# servo_tester.net
KiCad netlist of a schematic drawn in EAGLE
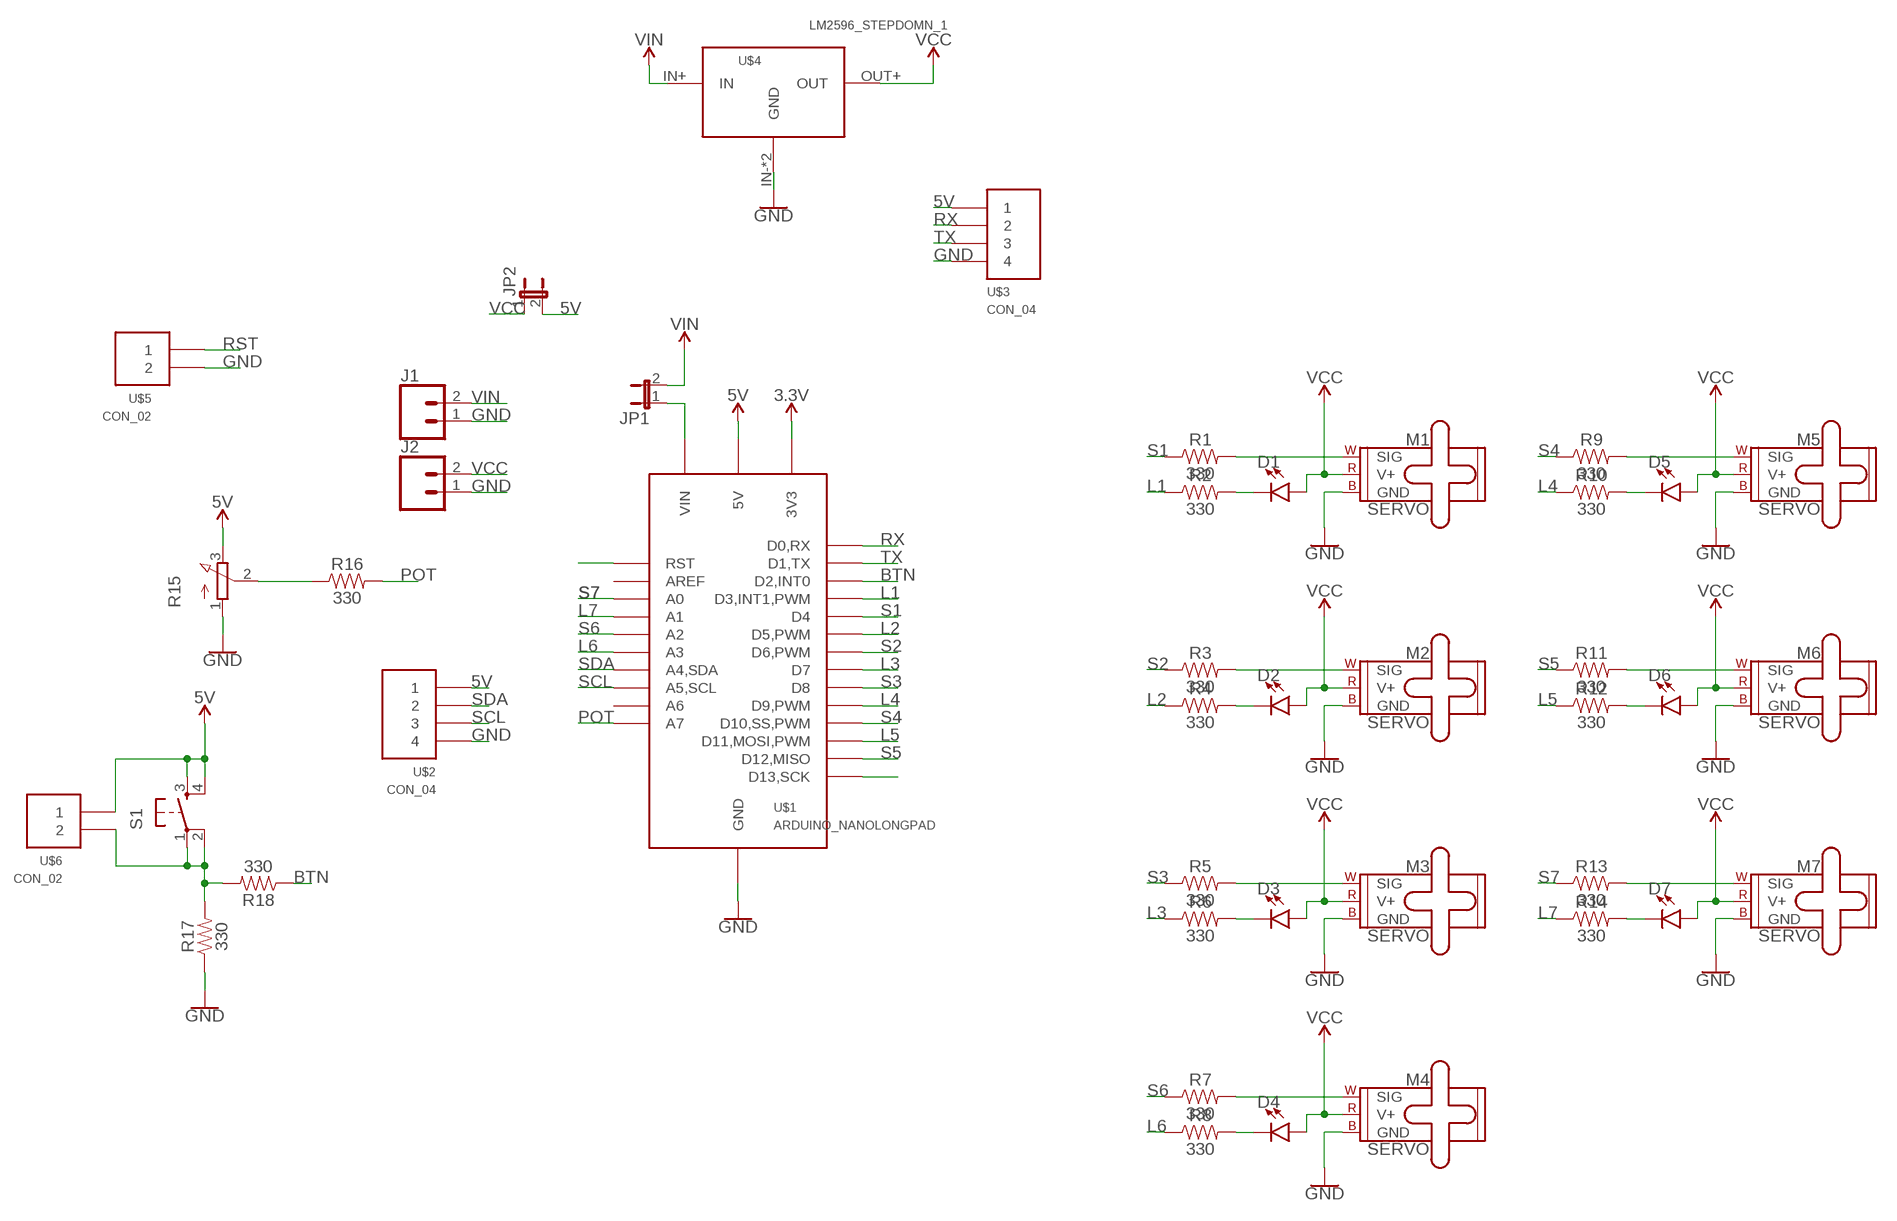
[diagram p0: schematic, sheet 1]

(export (version "E")
  (design (tool "Eeschema 10.0.6"))
  (components
    (comp (ref "D1")
      (value "LED3MM")
      (footprint "eagle-import:LED_3MM")
      (libsource (lib "eagle-import") (part "LED3MM"))
    )
    (comp (ref "D2")
      (value "LED3MM")
      (footprint "eagle-import:LED_3MM")
      (libsource (lib "eagle-import") (part "LED3MM"))
    )
    (comp (ref "D3")
      (value "LED3MM")
      (footprint "eagle-import:LED_3MM")
      (libsource (lib "eagle-import") (part "LED3MM"))
    )
    (comp (ref "D4")
      (value "LED3MM")
      (footprint "eagle-import:LED_3MM")
      (libsource (lib "eagle-import") (part "LED3MM"))
    )
    (comp (ref "D5")
      (value "LED3MM")
      (footprint "eagle-import:LED_3MM")
      (libsource (lib "eagle-import") (part "LED3MM"))
    )
    (comp (ref "D6")
      (value "LED3MM")
      (footprint "eagle-import:LED_3MM")
      (libsource (lib "eagle-import") (part "LED3MM"))
    )
    (comp (ref "D7")
      (value "LED3MM")
      (footprint "eagle-import:LED_3MM")
      (libsource (lib "eagle-import") (part "LED3MM"))
    )
    (comp (ref "J1")
      (value "CONN_025MM")
      (footprint "eagle-import:SCREWTERMINAL-5MM-2")
      (libsource (lib "eagle-import") (part "CONN_025MM"))
    )
    (comp (ref "J2")
      (value "CONN_025MM")
      (footprint "eagle-import:SCREWTERMINAL-5MM-2")
      (libsource (lib "eagle-import") (part "CONN_025MM"))
    )
    (comp (ref "JP1")
      (value "JUMPER-2PTH")
      (footprint "eagle-import:1X02")
      (libsource (lib "eagle-import") (part "JUMPER-2PTH"))
    )
    (comp (ref "JP2")
      (value "JUMPER-2PTH")
      (footprint "eagle-import:1X02")
      (libsource (lib "eagle-import") (part "JUMPER-2PTH"))
    )
    (comp (ref "M1")
      (value "SERVO")
      (footprint "eagle-import:1X03")
      (libsource (lib "eagle-import") (part "SERVO"))
    )
    (comp (ref "M2")
      (value "SERVO")
      (footprint "eagle-import:1X03")
      (libsource (lib "eagle-import") (part "SERVO"))
    )
    (comp (ref "M3")
      (value "SERVO")
      (footprint "eagle-import:1X03")
      (libsource (lib "eagle-import") (part "SERVO"))
    )
    (comp (ref "M4")
      (value "SERVO")
      (footprint "eagle-import:1X03")
      (libsource (lib "eagle-import") (part "SERVO"))
    )
    (comp (ref "M5")
      (value "SERVO")
      (footprint "eagle-import:1X03")
      (libsource (lib "eagle-import") (part "SERVO"))
    )
    (comp (ref "M6")
      (value "SERVO")
      (footprint "eagle-import:1X03")
      (libsource (lib "eagle-import") (part "SERVO"))
    )
    (comp (ref "M7")
      (value "SERVO")
      (footprint "eagle-import:1X03")
      (libsource (lib "eagle-import") (part "SERVO"))
    )
    (comp (ref "R1")
      (value "330")
      (footprint "eagle-import:0603")
      (libsource (lib "eagle-import") (part "330OHM-0603-1/10W-1%"))
    )
    (comp (ref "R2")
      (value "330")
      (footprint "eagle-import:0603")
      (libsource (lib "eagle-import") (part "330OHM-0603-1/10W-1%"))
    )
    (comp (ref "R3")
      (value "330")
      (footprint "eagle-import:0603")
      (libsource (lib "eagle-import") (part "330OHM-0603-1/10W-1%"))
    )
    (comp (ref "R4")
      (value "330")
      (footprint "eagle-import:0603")
      (libsource (lib "eagle-import") (part "330OHM-0603-1/10W-1%"))
    )
    (comp (ref "R5")
      (value "330")
      (footprint "eagle-import:0603")
      (libsource (lib "eagle-import") (part "330OHM-0603-1/10W-1%"))
    )
    (comp (ref "R6")
      (value "330")
      (footprint "eagle-import:0603")
      (libsource (lib "eagle-import") (part "330OHM-0603-1/10W-1%"))
    )
    (comp (ref "R7")
      (value "330")
      (footprint "eagle-import:0603")
      (libsource (lib "eagle-import") (part "330OHM-0603-1/10W-1%"))
    )
    (comp (ref "R8")
      (value "330")
      (footprint "eagle-import:0603")
      (libsource (lib "eagle-import") (part "330OHM-0603-1/10W-1%"))
    )
    (comp (ref "R9")
      (value "330")
      (footprint "eagle-import:0603")
      (libsource (lib "eagle-import") (part "330OHM-0603-1/10W-1%"))
    )
    (comp (ref "R10")
      (value "330")
      (footprint "eagle-import:0603")
      (libsource (lib "eagle-import") (part "330OHM-0603-1/10W-1%"))
    )
    (comp (ref "R11")
      (value "330")
      (footprint "eagle-import:0603")
      (libsource (lib "eagle-import") (part "330OHM-0603-1/10W-1%"))
    )
    (comp (ref "R12")
      (value "330")
      (footprint "eagle-import:0603")
      (libsource (lib "eagle-import") (part "330OHM-0603-1/10W-1%"))
    )
    (comp (ref "R13")
      (value "330")
      (footprint "eagle-import:0603")
      (libsource (lib "eagle-import") (part "330OHM-0603-1/10W-1%"))
    )
    (comp (ref "R14")
      (value "330")
      (footprint "eagle-import:0603")
      (libsource (lib "eagle-import") (part "330OHM-0603-1/10W-1%"))
    )
    (comp (ref "R15")
      (value "3RP/1610N")
      (footprint "eagle-import:3RP_1610N")
      (libsource (lib "eagle-import") (part "3RP/1610N"))
    )
    (comp (ref "R16")
      (value "330")
      (footprint "eagle-import:0603")
      (libsource (lib "eagle-import") (part "330OHM-0603-1/10W-1%"))
    )
    (comp (ref "R17")
      (value "330")
      (footprint "eagle-import:0603")
      (libsource (lib "eagle-import") (part "330OHM-0603-1/10W-1%"))
    )
    (comp (ref "R18")
      (value "330")
      (footprint "eagle-import:0603")
      (libsource (lib "eagle-import") (part "330OHM-0603-1/10W-1%"))
    )
    (comp (ref "S1")
      (value "TAC_SWITCHPTH")
      (footprint "eagle-import:TACTILE-PTH")
      (libsource (lib "eagle-import") (part "TAC_SWITCHPTH"))
    )
    (comp (ref "U$1")
      (value "ARDUINO_NANOLONGPAD")
      (footprint "eagle-import:ARDUINO_MANO_LONGPAD")
      (libsource (lib "eagle-import") (part "ARDUINO_NANOLONGPAD"))
    )
    (comp (ref "U$2")
      (value "CON_04")
      (footprint "eagle-import:4-PIN")
      (libsource (lib "eagle-import") (part "CON_04"))
    )
    (comp (ref "U$3")
      (value "CON_04")
      (footprint "eagle-import:4-PIN")
      (libsource (lib "eagle-import") (part "CON_04"))
    )
    (comp (ref "U$4")
      (value "LM2596_STEPDOMN_1")
      (footprint "eagle-import:STEPDOWN_1")
      (libsource (lib "eagle-import") (part "LM2596_STEPDOMN_1"))
    )
    (comp (ref "U$5")
      (value "CON_02")
      (footprint "eagle-import:2-PIN")
      (libsource (lib "eagle-import") (part "CON_02"))
    )
    (comp (ref "U$6")
      (value "CON_02")
      (footprint "eagle-import:2-PIN")
      (libsource (lib "eagle-import") (part "CON_02"))
    )
  )
  (nets
    (net (code "1") (name "/BTN") (class "Default")
      (node (ref "R18") (pin "1") (pinfunction "1_1") (pintype "passive"))
      (node (ref "U$1") (pin "D2") (pinfunction "D2,INT0_D2") (pintype "bidirectional"))
    )
    (net (code "2") (name "/L1") (class "Default")
      (node (ref "R2") (pin "1") (pinfunction "1_1") (pintype "passive"))
      (node (ref "U$1") (pin "D3") (pinfunction "D3,INT1,PWM_D3") (pintype "bidirectional"))
    )
    (net (code "3") (name "/L2") (class "Default")
      (node (ref "R4") (pin "1") (pinfunction "1_1") (pintype "passive"))
      (node (ref "U$1") (pin "D5") (pinfunction "D5,PWM_D5") (pintype "bidirectional"))
    )
    (net (code "4") (name "/L3") (class "Default")
      (node (ref "R6") (pin "1") (pinfunction "1_1") (pintype "passive"))
      (node (ref "U$1") (pin "D7") (pinfunction "D7_D7") (pintype "bidirectional"))
    )
    (net (code "5") (name "/L4") (class "Default")
      (node (ref "R10") (pin "1") (pinfunction "1_1") (pintype "passive"))
      (node (ref "U$1") (pin "D9") (pinfunction "D9,PWM_D9") (pintype "bidirectional"))
    )
    (net (code "6") (name "/L5") (class "Default")
      (node (ref "R12") (pin "1") (pinfunction "1_1") (pintype "passive"))
      (node (ref "U$1") (pin "D11") (pinfunction "D11,MOSI,PWM_D11") (pintype "bidirectional"))
    )
    (net (code "7") (name "/L6") (class "Default")
      (node (ref "R8") (pin "1") (pinfunction "1_1") (pintype "passive"))
      (node (ref "U$1") (pin "A3") (pinfunction "A3_A3") (pintype "bidirectional"))
    )
    (net (code "8") (name "/L7") (class "Default")
      (node (ref "R14") (pin "1") (pinfunction "1_1") (pintype "passive"))
      (node (ref "U$1") (pin "A1") (pinfunction "A1_A1") (pintype "bidirectional"))
    )
    (net (code "9") (name "/POT") (class "Default")
      (node (ref "R16") (pin "2") (pinfunction "2_2") (pintype "passive"))
      (node (ref "U$1") (pin "A7") (pinfunction "A7_A7") (pintype "bidirectional"))
    )
    (net (code "10") (name "/RST") (class "Default")
      (node (ref "U$1") (pin "RST@1") (pinfunction "RST_RST@1") (pintype "bidirectional"))
      (node (ref "U$1") (pin "RST@2") (pinfunction "RST_RST@2") (pintype "bidirectional"))
      (node (ref "U$5") (pin "1") (pinfunction "1_1") (pintype "bidirectional"))
    )
    (net (code "11") (name "/RX") (class "Default")
      (node (ref "U$1") (pin "RX0") (pinfunction "D0,RX_RX0") (pintype "bidirectional"))
      (node (ref "U$3") (pin "2") (pinfunction "2_2") (pintype "bidirectional"))
    )
    (net (code "12") (name "/S1") (class "Default")
      (node (ref "R1") (pin "1") (pinfunction "1_1") (pintype "passive"))
      (node (ref "U$1") (pin "D4") (pinfunction "D4_D4") (pintype "bidirectional"))
    )
    (net (code "13") (name "/S2") (class "Default")
      (node (ref "R3") (pin "1") (pinfunction "1_1") (pintype "passive"))
      (node (ref "U$1") (pin "D6") (pinfunction "D6,PWM_D6") (pintype "bidirectional"))
    )
    (net (code "14") (name "/S3") (class "Default")
      (node (ref "R5") (pin "1") (pinfunction "1_1") (pintype "passive"))
      (node (ref "U$1") (pin "D8") (pinfunction "D8_D8") (pintype "bidirectional"))
    )
    (net (code "15") (name "/S4") (class "Default")
      (node (ref "R9") (pin "1") (pinfunction "1_1") (pintype "passive"))
      (node (ref "U$1") (pin "D10") (pinfunction "D10,SS,PWM_D10") (pintype "bidirectional"))
    )
    (net (code "16") (name "/S5") (class "Default")
      (node (ref "R11") (pin "1") (pinfunction "1_1") (pintype "passive"))
      (node (ref "U$1") (pin "D12") (pinfunction "D12,MISO_D12") (pintype "bidirectional"))
    )
    (net (code "17") (name "/S6") (class "Default")
      (node (ref "R7") (pin "1") (pinfunction "1_1") (pintype "passive"))
      (node (ref "U$1") (pin "A2") (pinfunction "A2_A2") (pintype "bidirectional"))
    )
    (net (code "18") (name "/S7") (class "Default")
      (node (ref "R13") (pin "1") (pinfunction "1_1") (pintype "passive"))
      (node (ref "U$1") (pin "A0") (pinfunction "A0_A0") (pintype "bidirectional"))
    )
    (net (code "19") (name "/SCL") (class "Default")
      (node (ref "U$1") (pin "A5") (pinfunction "A5,SCL_A5") (pintype "bidirectional"))
      (node (ref "U$2") (pin "3") (pinfunction "3_3") (pintype "bidirectional"))
    )
    (net (code "20") (name "/SDA") (class "Default")
      (node (ref "U$1") (pin "A4") (pinfunction "A4,SDA_A4") (pintype "bidirectional"))
      (node (ref "U$2") (pin "2") (pinfunction "2_2") (pintype "bidirectional"))
    )
    (net (code "21") (name "/TX") (class "Default")
      (node (ref "U$1") (pin "TX1") (pinfunction "D1,TX_TX1") (pintype "bidirectional"))
      (node (ref "U$3") (pin "3") (pinfunction "3_3") (pintype "bidirectional"))
    )
    (net (code "22") (name "3.3V") (class "Default")
      (node (ref "U$1") (pin "3V3") (pinfunction "3V3_3V3") (pintype "bidirectional"))
    )
    (net (code "23") (name "5V") (class "Default")
      (node (ref "JP2") (pin "2") (pinfunction "2_2") (pintype "passive"))
      (node (ref "R15") (pin "3") (pinfunction "E_3") (pintype "passive"))
      (node (ref "S1") (pin "3") (pinfunction "3_3") (pintype "passive"))
      (node (ref "S1") (pin "4") (pinfunction "4_4") (pintype "passive"))
      (node (ref "U$1") (pin "5V") (pinfunction "5V_5V") (pintype "bidirectional"))
      (node (ref "U$2") (pin "1") (pinfunction "1_1") (pintype "bidirectional"))
      (node (ref "U$3") (pin "1") (pinfunction "1_1") (pintype "bidirectional"))
      (node (ref "U$6") (pin "1") (pinfunction "1_1") (pintype "bidirectional"))
    )
    (net (code "24") (name "GND") (class "Default")
      (node (ref "J1") (pin "1") (pinfunction "1_1") (pintype "passive"))
      (node (ref "J2") (pin "1") (pinfunction "1_1") (pintype "passive"))
      (node (ref "M1") (pin "3") (pinfunction "GND_3") (pintype "bidirectional"))
      (node (ref "M2") (pin "3") (pinfunction "GND_3") (pintype "bidirectional"))
      (node (ref "M3") (pin "3") (pinfunction "GND_3") (pintype "bidirectional"))
      (node (ref "M4") (pin "3") (pinfunction "GND_3") (pintype "bidirectional"))
      (node (ref "M5") (pin "3") (pinfunction "GND_3") (pintype "bidirectional"))
      (node (ref "M6") (pin "3") (pinfunction "GND_3") (pintype "bidirectional"))
      (node (ref "M7") (pin "3") (pinfunction "GND_3") (pintype "bidirectional"))
      (node (ref "R15") (pin "1") (pinfunction "A_1") (pintype "passive"))
      (node (ref "R17") (pin "1") (pinfunction "1_1") (pintype "passive"))
      (node (ref "U$1") (pin "GND@1") (pinfunction "GND_GND@1") (pintype "bidirectional"))
      (node (ref "U$1") (pin "GND@2") (pinfunction "GND_GND@2") (pintype "bidirectional"))
      (node (ref "U$2") (pin "4") (pinfunction "4_4") (pintype "bidirectional"))
      (node (ref "U$3") (pin "4") (pinfunction "4_4") (pintype "bidirectional"))
      (node (ref "U$4") (pin "IN-") (pinfunction "GND_IN-") (pintype "bidirectional"))
      (node (ref "U$4") (pin "OUT-") (pinfunction "GND_OUT-") (pintype "bidirectional"))
      (node (ref "U$5") (pin "2") (pinfunction "2_2") (pintype "bidirectional"))
    )
    (net (code "25") (name "Net-(D1-C)") (class "Default")
      (node (ref "D1") (pin "K") (pinfunction "C_K") (pintype "passive"))
      (node (ref "R2") (pin "2") (pinfunction "2_2") (pintype "passive"))
    )
    (net (code "26") (name "Net-(D2-C)") (class "Default")
      (node (ref "D2") (pin "K") (pinfunction "C_K") (pintype "passive"))
      (node (ref "R4") (pin "2") (pinfunction "2_2") (pintype "passive"))
    )
    (net (code "27") (name "Net-(D3-C)") (class "Default")
      (node (ref "D3") (pin "K") (pinfunction "C_K") (pintype "passive"))
      (node (ref "R6") (pin "2") (pinfunction "2_2") (pintype "passive"))
    )
    (net (code "28") (name "Net-(D4-C)") (class "Default")
      (node (ref "D4") (pin "K") (pinfunction "C_K") (pintype "passive"))
      (node (ref "R8") (pin "2") (pinfunction "2_2") (pintype "passive"))
    )
    (net (code "29") (name "Net-(D5-C)") (class "Default")
      (node (ref "D5") (pin "K") (pinfunction "C_K") (pintype "passive"))
      (node (ref "R10") (pin "2") (pinfunction "2_2") (pintype "passive"))
    )
    (net (code "30") (name "Net-(D6-C)") (class "Default")
      (node (ref "D6") (pin "K") (pinfunction "C_K") (pintype "passive"))
      (node (ref "R12") (pin "2") (pinfunction "2_2") (pintype "passive"))
    )
    (net (code "31") (name "Net-(D7-C)") (class "Default")
      (node (ref "D7") (pin "K") (pinfunction "C_K") (pintype "passive"))
      (node (ref "R14") (pin "2") (pinfunction "2_2") (pintype "passive"))
    )
    (net (code "32") (name "Net-(JP1-Pad1)") (class "Default")
      (node (ref "JP1") (pin "1") (pinfunction "1_1") (pintype "passive"))
      (node (ref "U$1") (pin "VIN") (pinfunction "VIN_VIN") (pintype "bidirectional"))
    )
    (net (code "33") (name "Net-(M1-SIG)") (class "Default")
      (node (ref "M1") (pin "1") (pinfunction "SIG_1") (pintype "bidirectional"))
      (node (ref "R1") (pin "2") (pinfunction "2_2") (pintype "passive"))
    )
    (net (code "34") (name "Net-(M2-SIG)") (class "Default")
      (node (ref "M2") (pin "1") (pinfunction "SIG_1") (pintype "bidirectional"))
      (node (ref "R3") (pin "2") (pinfunction "2_2") (pintype "passive"))
    )
    (net (code "35") (name "Net-(M3-SIG)") (class "Default")
      (node (ref "M3") (pin "1") (pinfunction "SIG_1") (pintype "bidirectional"))
      (node (ref "R5") (pin "2") (pinfunction "2_2") (pintype "passive"))
    )
    (net (code "36") (name "Net-(M4-SIG)") (class "Default")
      (node (ref "M4") (pin "1") (pinfunction "SIG_1") (pintype "bidirectional"))
      (node (ref "R7") (pin "2") (pinfunction "2_2") (pintype "passive"))
    )
    (net (code "37") (name "Net-(M5-SIG)") (class "Default")
      (node (ref "M5") (pin "1") (pinfunction "SIG_1") (pintype "bidirectional"))
      (node (ref "R9") (pin "2") (pinfunction "2_2") (pintype "passive"))
    )
    (net (code "38") (name "Net-(M6-SIG)") (class "Default")
      (node (ref "M6") (pin "1") (pinfunction "SIG_1") (pintype "bidirectional"))
      (node (ref "R11") (pin "2") (pinfunction "2_2") (pintype "passive"))
    )
    (net (code "39") (name "Net-(M7-SIG)") (class "Default")
      (node (ref "M7") (pin "1") (pinfunction "SIG_1") (pintype "bidirectional"))
      (node (ref "R13") (pin "2") (pinfunction "2_2") (pintype "passive"))
    )
    (net (code "40") (name "Net-(R15-S)") (class "Default")
      (node (ref "R15") (pin "2") (pinfunction "S_2") (pintype "passive"))
      (node (ref "R16") (pin "1") (pinfunction "1_1") (pintype "passive"))
    )
    (net (code "41") (name "Net-(R17-Pad2)") (class "Default")
      (node (ref "R17") (pin "2") (pinfunction "2_2") (pintype "passive"))
      (node (ref "R18") (pin "2") (pinfunction "2_2") (pintype "passive"))
      (node (ref "S1") (pin "1") (pinfunction "1_1") (pintype "passive"))
      (node (ref "S1") (pin "2") (pinfunction "2_2") (pintype "passive"))
      (node (ref "U$6") (pin "2") (pinfunction "2_2") (pintype "bidirectional"))
    )
    (net (code "42") (name "VCC") (class "Default")
      (node (ref "D1") (pin "A") (pinfunction "A_A") (pintype "passive"))
      (node (ref "D2") (pin "A") (pinfunction "A_A") (pintype "passive"))
      (node (ref "D3") (pin "A") (pinfunction "A_A") (pintype "passive"))
      (node (ref "D4") (pin "A") (pinfunction "A_A") (pintype "passive"))
      (node (ref "D5") (pin "A") (pinfunction "A_A") (pintype "passive"))
      (node (ref "D6") (pin "A") (pinfunction "A_A") (pintype "passive"))
      (node (ref "D7") (pin "A") (pinfunction "A_A") (pintype "passive"))
      (node (ref "J2") (pin "2") (pinfunction "2_2") (pintype "passive"))
      (node (ref "JP2") (pin "1") (pinfunction "1_1") (pintype "passive"))
      (node (ref "M1") (pin "2") (pinfunction "V+_2") (pintype "bidirectional"))
      (node (ref "M2") (pin "2") (pinfunction "V+_2") (pintype "bidirectional"))
      (node (ref "M3") (pin "2") (pinfunction "V+_2") (pintype "bidirectional"))
      (node (ref "M4") (pin "2") (pinfunction "V+_2") (pintype "bidirectional"))
      (node (ref "M5") (pin "2") (pinfunction "V+_2") (pintype "bidirectional"))
      (node (ref "M6") (pin "2") (pinfunction "V+_2") (pintype "bidirectional"))
      (node (ref "M7") (pin "2") (pinfunction "V+_2") (pintype "bidirectional"))
      (node (ref "U$4") (pin "OUT+") (pinfunction "OUT_OUT+") (pintype "bidirectional"))
    )
    (net (code "43") (name "VIN") (class "Default")
      (node (ref "J1") (pin "2") (pinfunction "2_2") (pintype "passive"))
      (node (ref "JP1") (pin "2") (pinfunction "2_2") (pintype "passive"))
      (node (ref "U$4") (pin "IN+") (pinfunction "IN_IN+") (pintype "bidirectional"))
    )
    (net (code "44") (name "unconnected-(U$1-D13,SCK-PadD13)") (class "Default")
      (node (ref "U$1") (pin "D13") (pinfunction "D13,SCK_D13") (pintype "bidirectional"))
    )
    (net (code "45") (name "unconnected-(U$1-PadA6)") (class "Default")
      (node (ref "U$1") (pin "A6") (pinfunction "A6_A6") (pintype "bidirectional"))
    )
    (net (code "46") (name "unconnected-(U$1-PadAREF)") (class "Default")
      (node (ref "U$1") (pin "AREF") (pinfunction "AREF_AREF") (pintype "bidirectional"))
    )
  )
)
